# CPU.net
KiCad netlist of a schematic drawn in Altium Designer
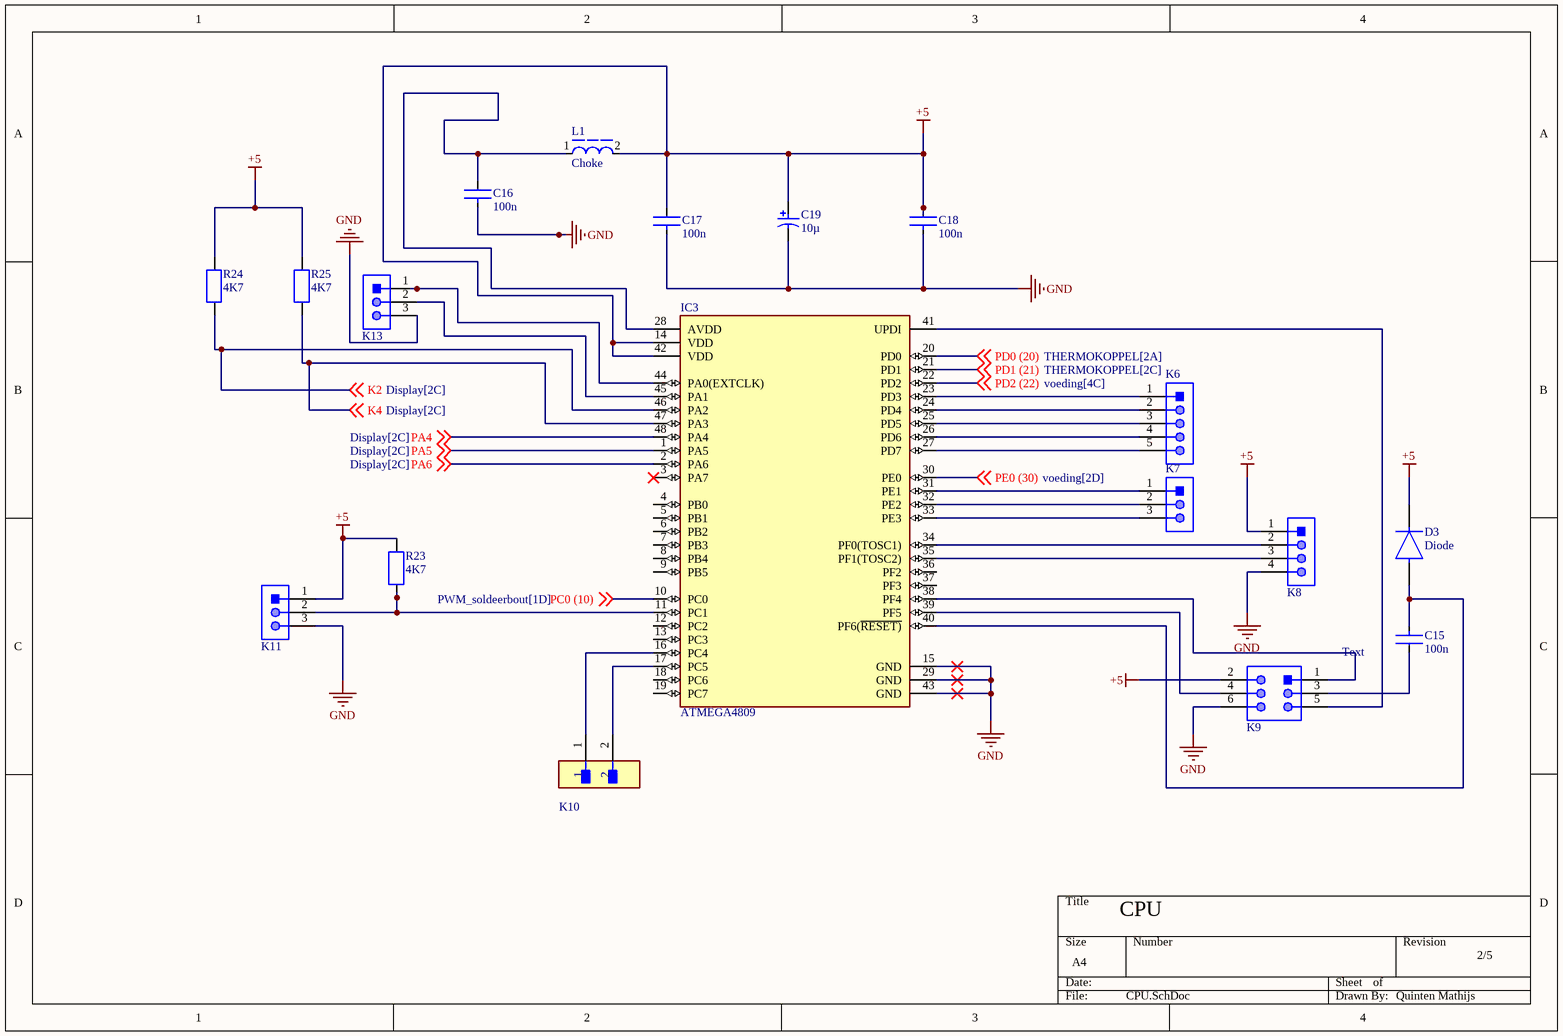
[diagram p0: CPU.SchDoc]

(export (version "E")
  (design (tool "Eeschema 10.0.6"))
  (components
    (comp (ref "C15")
      (value "100n")
      (footprint "CC_0805_L")
      (fields
        (field (name "MANUFACTURER") "KEMET")
        (field (name "OCTOPART") "https://octopart.com/c0805c224k5ractu-kemet-144670")
        (field (name "MANUFACTURER PART NUMBER") "C0805C224K5RACTU")
      )
      (libsource (lib "Schem_Soldeerstation") (part "Capacitor_Ceramic"))
    )
    (comp (ref "C16")
      (value "100n")
      (footprint "CC_0805_L")
      (fields
        (field (name "MANUFACTURER") "KEMET")
        (field (name "OCTOPART") "https://octopart.com/c0805c224k5ractu-kemet-144670")
        (field (name "MANUFACTURER PART NUMBER") "C0805C224K5RACTU")
      )
      (libsource (lib "Schem_Soldeerstation") (part "Capacitor_Ceramic"))
    )
    (comp (ref "C17")
      (value "100n")
      (footprint "CC_0805_L")
      (fields
        (field (name "MANUFACTURER") "KEMET")
        (field (name "OCTOPART") "https://octopart.com/c0805c224k5ractu-kemet-144670")
        (field (name "MANUFACTURER PART NUMBER") "C0805C224K5RACTU")
      )
      (libsource (lib "Schem_Soldeerstation") (part "Capacitor_Ceramic"))
    )
    (comp (ref "C18")
      (value "100n")
      (footprint "CC_0805_L")
      (fields
        (field (name "MANUFACTURER") "KEMET")
        (field (name "OCTOPART") "https://octopart.com/c0805c224k5ractu-kemet-144670")
        (field (name "MANUFACTURER PART NUMBER") "C0805C224K5RACTU")
      )
      (libsource (lib "Schem_Soldeerstation") (part "Capacitor_Ceramic"))
    )
    (comp (ref "C19")
      (value "10µ")
      (footprint "CE_D8_L10")
      (fields (field (name "MANUFACTURER") "Panasonic"))
      (libsource (lib "Schem_Soldeerstation") (part "Capacitor_Electrolytic"))
    )
    (comp (ref "D3")
      (value "Diode")
      (footprint "SOD-123FL")
      (fields
        (field (name "MANUFACTURER PART NUMBER") "1N4007")
        (field (name "MANUFACTURER") "Diotec")
        (field (name "OCTOPART") "https://octopart.com/1n4007-diotec-4040411")
      )
      (libsource (lib "Schem_Soldeerstation") (part "Diode"))
    )
    (comp (ref "IC3")
      (value "ATMEGA4809")
      (footprint "TQFP_48_M")
      (libsource (lib "Schem_Soldeerstation") (part "ATMEGA4809"))
    )
    (comp (ref "K6")
      (value "~")
      (footprint "pin header 1x5")
      (description "THT Vertical Pin Header WR-PHD, Pitch 2.54 mm, Single Row, 5 pins")
      (fields
        (field (name "PART NUMBER") "61300511121")
        (field (name "MANUFACTURER") "Wurth Elektronik")
        (field (name "PUBLISHER") "WurthElektronik")
      )
      (libsource (lib "Schem_Soldeerstation") (part "pin header 1x5"))
    )
    (comp (ref "K7")
      (value "~")
      (footprint "pin header 1x3")
      (description "THT Vertical Pin Header WR-PHD, Pitch 2.54 mm, Single Row, 3 pins")
      (fields
        (field (name "PART NUMBER") "61300311121")
        (field (name "MANUFACTURER") "Wurth Elektronik")
        (field (name "PUBLISHER") "WurthElektronik")
      )
      (libsource (lib "") (part "pin header 1x3pin_1"))
    )
    (comp (ref "K8")
      (value "61300411121")
      (footprint "pin header 1x4")
      (description "THT Vertical Pin Header WR-PHD, Pitch 2.54 mm, Single Row, 4 pins")
      (fields (field (name "MANUFACTURER") "Wurth Elektronik") (field (name "PUBLISHER") "WurthElektronik"))
      (libsource (lib "Schem_Soldeerstation") (part "pin header 1x4"))
    )
    (comp (ref "K9")
      (value "61300621121")
      (footprint "pin header 2x6")
      (description "THT Vertical Pin Header WR-PHD, Pitch 2.54 mm, Dual Row, 6 pins")
      (fields (field (name "MANUFACTURER") "Wurth Elektronik") (field (name "PUBLISHER") "WurthElektronik"))
      (libsource (lib "Schem_Soldeerstation") (part "pin header 2x6"))
    )
    (comp (ref "K10")
      (value "M20-9990246")
      (footprint "pin header 1x2")
      (description "CONN HEADER VERT 2POS 2.54MM")
      (fields
        (field (name "OCTOPART") "https://octopart.com/m20-9990246-harwin-2590635")
        (field (name "MANUFACTURER") "Harwin")
      )
      (libsource (lib "Schem_Soldeerstation") (part "pin header 1x2"))
    )
    (comp (ref "K11")
      (value "61300311121")
      (footprint "pin header 1x3")
      (description "THT Vertical Pin Header WR-PHD, Pitch 2.54 mm, Single Row, 3 pins")
      (fields (field (name "MANUFACTURER") "Wurth Elektronik") (field (name "PUBLISHER") "WurthElektronik"))
      (libsource (lib "Schem_Soldeerstation") (part "pin header 1x3pin"))
    )
    (comp (ref "K13")
      (value "61300311121")
      (footprint "pin header 1x3")
      (description "THT Vertical Pin Header WR-PHD, Pitch 2.54 mm, Single Row, 3 pins")
      (fields (field (name "MANUFACTURER") "Wurth Elektronik") (field (name "PUBLISHER") "WurthElektronik"))
      (libsource (lib "Schem_Soldeerstation") (part "pin header 1x3pin"))
    )
    (comp (ref "L1")
      (value "Choke")
      (footprint "CC_0805_L")
      (description "smoorspoel")
      (fields (field (name "TOLERANCE") "20%"))
      (libsource (lib "Schem_Soldeerstation") (part "Choke"))
    )
    (comp (ref "R23")
      (value "4K7")
      (footprint "R_0805_L")
      (description "Resistor")
      (fields (field (name "MANUFACTURER") "Vishay Dale") (field (name "PART NUMBER") "CRCW08050000Z0EA"))
      (libsource (lib "Schem_Soldeerstation") (part "0805 (Resistor)"))
    )
    (comp (ref "R24")
      (value "4K7")
      (footprint "R_0805_L")
      (description "Resistor")
      (fields (field (name "MANUFACTURER") "Vishay Dale") (field (name "PART NUMBER") "CRCW08050000Z0EA"))
      (libsource (lib "Schem_Soldeerstation") (part "0805 (Resistor)"))
    )
    (comp (ref "R25")
      (value "4K7")
      (footprint "R_0805_L")
      (description "Resistor")
      (fields (field (name "MANUFACTURER") "Vishay Dale") (field (name "PART NUMBER") "CRCW08050000Z0EA"))
      (libsource (lib "Schem_Soldeerstation") (part "0805 (Resistor)"))
    )
  )
  (nets
    (net (code "1") (name "+5") (class "Default")
      (node (ref "C17") (pin "2") (pinfunction "2_2") (pintype "passive"))
      (node (ref "C18") (pin "2") (pinfunction "2_2") (pintype "passive"))
      (node (ref "C19") (pin "2") (pinfunction "2_2") (pintype "passive"))
      (node (ref "D3") (pin "1") (pinfunction "C_1") (pintype "passive"))
      (node (ref "IC3") (pin "14") (pinfunction "VDD_14") (pintype "power_in"))
      (node (ref "IC3") (pin "42") (pinfunction "VDD_42") (pintype "power_in"))
      (node (ref "K11") (pin "1") (pinfunction "1_1") (pintype "passive"))
      (node (ref "K8") (pin "1") (pinfunction "1_1") (pintype "passive"))
      (node (ref "K9") (pin "2") (pinfunction "2_2") (pintype "passive"))
      (node (ref "L1") (pin "2") (pinfunction "2_2") (pintype "passive"))
      (node (ref "R23") (pin "2") (pinfunction "2_2") (pintype "passive"))
      (node (ref "R24") (pin "2") (pinfunction "2_2") (pintype "passive"))
      (node (ref "R25") (pin "2") (pinfunction "2_2") (pintype "passive"))
    )
    (net (code "2") (name "GND") (class "Default")
      (node (ref "C16") (pin "1") (pinfunction "1_1") (pintype "passive"))
      (node (ref "C17") (pin "1") (pinfunction "1_1") (pintype "passive"))
      (node (ref "C18") (pin "1") (pinfunction "1_1") (pintype "passive"))
      (node (ref "C19") (pin "1") (pinfunction "1_1") (pintype "passive"))
      (node (ref "IC3") (pin "15") (pinfunction "GND_15") (pintype "open_emitter"))
      (node (ref "IC3") (pin "29") (pinfunction "GND_29") (pintype "power_in"))
      (node (ref "IC3") (pin "43") (pinfunction "GND_43") (pintype "power_in"))
      (node (ref "K11") (pin "3") (pinfunction "3_3") (pintype "passive"))
      (node (ref "K13") (pin "3") (pinfunction "3_3") (pintype "passive"))
      (node (ref "K8") (pin "4") (pinfunction "4_4") (pintype "passive"))
      (node (ref "K9") (pin "6") (pinfunction "6_6") (pintype "passive"))
    )
    (net (code "3") (name "K2") (class "Default")
      (node (ref "IC3") (pin "46") (pinfunction "PA2_46") (pintype "bidirectional"))
      (node (ref "R24") (pin "1") (pinfunction "1_1") (pintype "passive"))
    )
    (net (code "4") (name "K4") (class "Default")
      (node (ref "IC3") (pin "47") (pinfunction "PA3_47") (pintype "bidirectional"))
      (node (ref "R25") (pin "1") (pinfunction "1_1") (pintype "passive"))
    )
    (net (code "5") (name "Net-(C15-Pad2)") (class "Default")
      (node (ref "C15") (pin "2") (pinfunction "2_2") (pintype "passive"))
      (node (ref "K9") (pin "3") (pinfunction "3_3") (pintype "passive"))
    )
    (net (code "6") (name "Net-(D3-A)") (class "Default")
      (node (ref "C15") (pin "1") (pinfunction "1_1") (pintype "passive"))
      (node (ref "D3") (pin "2") (pinfunction "A_2") (pintype "passive"))
      (node (ref "IC3") (pin "40") (pinfunction "PF6(~{RESET)}_40") (pintype "bidirectional"))
    )
    (net (code "7") (name "Net-(IC3-AVDD)") (class "Default")
      (node (ref "C16") (pin "2") (pinfunction "2_2") (pintype "passive"))
      (node (ref "IC3") (pin "28") (pinfunction "AVDD_28") (pintype "power_in"))
      (node (ref "L1") (pin "1") (pinfunction "1_1") (pintype "passive"))
    )
    (net (code "8") (name "Net-(IC3-PA0(EXTCLK))") (class "Default")
      (node (ref "IC3") (pin "44") (pinfunction "PA0(EXTCLK)_44") (pintype "bidirectional"))
      (node (ref "K13") (pin "1") (pinfunction "1_1") (pintype "passive"))
    )
    (net (code "9") (name "Net-(IC3-PA1)") (class "Default")
      (node (ref "IC3") (pin "45") (pinfunction "PA1_45") (pintype "bidirectional"))
      (node (ref "K13") (pin "2") (pinfunction "2_2") (pintype "passive"))
    )
    (net (code "10") (name "Net-(IC3-PC1)") (class "Default")
      (node (ref "IC3") (pin "11") (pinfunction "PC1_11") (pintype "bidirectional"))
      (node (ref "K11") (pin "2") (pinfunction "2_2") (pintype "passive"))
      (node (ref "R23") (pin "1") (pinfunction "1_1") (pintype "passive"))
    )
    (net (code "11") (name "Net-(IC3-PC4)") (class "Default")
      (node (ref "IC3") (pin "16") (pinfunction "PC4_16") (pintype "bidirectional"))
      (node (ref "K10") (pin "1") (pinfunction "1_1") (pintype "passive"))
    )
    (net (code "12") (name "Net-(IC3-PC5)") (class "Default")
      (node (ref "IC3") (pin "17") (pinfunction "PC5_17") (pintype "bidirectional"))
      (node (ref "K10") (pin "2") (pinfunction "2_2") (pintype "passive"))
    )
    (net (code "13") (name "Net-(IC3-PD3)") (class "Default")
      (node (ref "IC3") (pin "23") (pinfunction "PD3_23") (pintype "bidirectional"))
      (node (ref "K6") (pin "1") (pinfunction "1_1") (pintype "passive"))
    )
    (net (code "14") (name "Net-(IC3-PD4)") (class "Default")
      (node (ref "IC3") (pin "24") (pinfunction "PD4_24") (pintype "bidirectional"))
      (node (ref "K6") (pin "2") (pinfunction "2_2") (pintype "passive"))
    )
    (net (code "15") (name "Net-(IC3-PD5)") (class "Default")
      (node (ref "IC3") (pin "25") (pinfunction "PD5_25") (pintype "bidirectional"))
      (node (ref "K6") (pin "3") (pinfunction "3_3") (pintype "passive"))
    )
    (net (code "16") (name "Net-(IC3-PD6)") (class "Default")
      (node (ref "IC3") (pin "26") (pinfunction "PD6_26") (pintype "bidirectional"))
      (node (ref "K6") (pin "4") (pinfunction "4_4") (pintype "passive"))
    )
    (net (code "17") (name "Net-(IC3-PD7)") (class "Default")
      (node (ref "IC3") (pin "27") (pinfunction "PD7_27") (pintype "bidirectional"))
      (node (ref "K6") (pin "5") (pinfunction "5_5") (pintype "passive"))
    )
    (net (code "18") (name "Net-(IC3-PE1)") (class "Default")
      (node (ref "IC3") (pin "31") (pinfunction "PE1_31") (pintype "bidirectional"))
      (node (ref "K7") (pin "1") (pinfunction "1_1") (pintype "passive"))
    )
    (net (code "19") (name "Net-(IC3-PE2)") (class "Default")
      (node (ref "IC3") (pin "32") (pinfunction "PE2_32") (pintype "bidirectional"))
      (node (ref "K7") (pin "2") (pinfunction "2_2") (pintype "passive"))
    )
    (net (code "20") (name "Net-(IC3-PE3)") (class "Default")
      (node (ref "IC3") (pin "33") (pinfunction "PE3_33") (pintype "bidirectional"))
      (node (ref "K7") (pin "3") (pinfunction "3_3") (pintype "passive"))
    )
    (net (code "21") (name "Net-(IC3-PF0(TOSC1))") (class "Default")
      (node (ref "IC3") (pin "34") (pinfunction "PF0(TOSC1)_34") (pintype "bidirectional"))
      (node (ref "K8") (pin "2") (pinfunction "2_2") (pintype "passive"))
    )
    (net (code "22") (name "Net-(IC3-PF1(TOSC2))") (class "Default")
      (node (ref "IC3") (pin "35") (pinfunction "PF1(TOSC2)_35") (pintype "bidirectional"))
      (node (ref "K8") (pin "3") (pinfunction "3_3") (pintype "passive"))
    )
    (net (code "23") (name "Net-(IC3-PF4)") (class "Default")
      (node (ref "IC3") (pin "38") (pinfunction "PF4_38") (pintype "bidirectional"))
      (node (ref "K9") (pin "1") (pinfunction "1_1") (pintype "passive"))
    )
    (net (code "24") (name "Net-(IC3-PF5)") (class "Default")
      (node (ref "IC3") (pin "39") (pinfunction "PF5_39") (pintype "bidirectional"))
      (node (ref "K9") (pin "4") (pinfunction "4_4") (pintype "passive"))
    )
    (net (code "25") (name "Net-(IC3-UPDI)") (class "Default")
      (node (ref "IC3") (pin "41") (pinfunction "UPDI_41") (pintype "passive"))
      (node (ref "K9") (pin "5") (pinfunction "5_5") (pintype "passive"))
    )
    (net (code "26") (name "PA4") (class "Default")
      (node (ref "IC3") (pin "48") (pinfunction "PA4_48") (pintype "bidirectional"))
    )
    (net (code "27") (name "PA5") (class "Default")
      (node (ref "IC3") (pin "1") (pinfunction "PA5_1") (pintype "bidirectional"))
    )
    (net (code "28") (name "PA6") (class "Default")
      (node (ref "IC3") (pin "2") (pinfunction "PA6_2") (pintype "bidirectional"))
    )
    (net (code "29") (name "PC0 (10)") (class "Default")
      (node (ref "IC3") (pin "10") (pinfunction "PC0_10") (pintype "bidirectional"))
    )
    (net (code "30") (name "PD0 (20)") (class "Default")
      (node (ref "IC3") (pin "20") (pinfunction "PD0_20") (pintype "bidirectional"))
    )
    (net (code "31") (name "PD1 (21)") (class "Default")
      (node (ref "IC3") (pin "21") (pinfunction "PD1_21") (pintype "bidirectional"))
    )
    (net (code "32") (name "PD2 (22)") (class "Default")
      (node (ref "IC3") (pin "22") (pinfunction "PD2_22") (pintype "bidirectional"))
    )
    (net (code "33") (name "PE0 (30)") (class "Default")
      (node (ref "IC3") (pin "30") (pinfunction "PE0_30") (pintype "bidirectional"))
    )
    (net (code "34") (name "unconnected-(IC3-PA7-Pad3)") (class "Default")
      (node (ref "IC3") (pin "3") (pinfunction "PA7_3") (pintype "bidirectional+no_connect"))
    )
    (net (code "35") (name "unconnected-(IC3-PB0-Pad4)") (class "Default")
      (node (ref "IC3") (pin "4") (pinfunction "PB0_4") (pintype "bidirectional"))
    )
    (net (code "36") (name "unconnected-(IC3-PB1-Pad5)") (class "Default")
      (node (ref "IC3") (pin "5") (pinfunction "PB1_5") (pintype "bidirectional"))
    )
    (net (code "37") (name "unconnected-(IC3-PB2-Pad6)") (class "Default")
      (node (ref "IC3") (pin "6") (pinfunction "PB2_6") (pintype "bidirectional"))
    )
    (net (code "38") (name "unconnected-(IC3-PB3-Pad7)") (class "Default")
      (node (ref "IC3") (pin "7") (pinfunction "PB3_7") (pintype "bidirectional"))
    )
    (net (code "39") (name "unconnected-(IC3-PB4-Pad8)") (class "Default")
      (node (ref "IC3") (pin "8") (pinfunction "PB4_8") (pintype "bidirectional"))
    )
    (net (code "40") (name "unconnected-(IC3-PB5-Pad9)") (class "Default")
      (node (ref "IC3") (pin "9") (pinfunction "PB5_9") (pintype "bidirectional"))
    )
    (net (code "41") (name "unconnected-(IC3-PC2-Pad12)") (class "Default")
      (node (ref "IC3") (pin "12") (pinfunction "PC2_12") (pintype "bidirectional"))
    )
    (net (code "42") (name "unconnected-(IC3-PC3-Pad13)") (class "Default")
      (node (ref "IC3") (pin "13") (pinfunction "PC3_13") (pintype "bidirectional"))
    )
    (net (code "43") (name "unconnected-(IC3-PC6-Pad18)") (class "Default")
      (node (ref "IC3") (pin "18") (pinfunction "PC6_18") (pintype "bidirectional"))
    )
    (net (code "44") (name "unconnected-(IC3-PC7-Pad19)") (class "Default")
      (node (ref "IC3") (pin "19") (pinfunction "PC7_19") (pintype "bidirectional"))
    )
    (net (code "45") (name "unconnected-(IC3-PF2-Pad36)") (class "Default")
      (node (ref "IC3") (pin "36") (pinfunction "PF2_36") (pintype "bidirectional"))
    )
    (net (code "46") (name "unconnected-(IC3-PF3-Pad37)") (class "Default")
      (node (ref "IC3") (pin "37") (pinfunction "PF3_37") (pintype "bidirectional"))
    )
  )
)
